# SnekHeaderBoard.net
KiCad netlist of a schematic drawn in Altium Designer
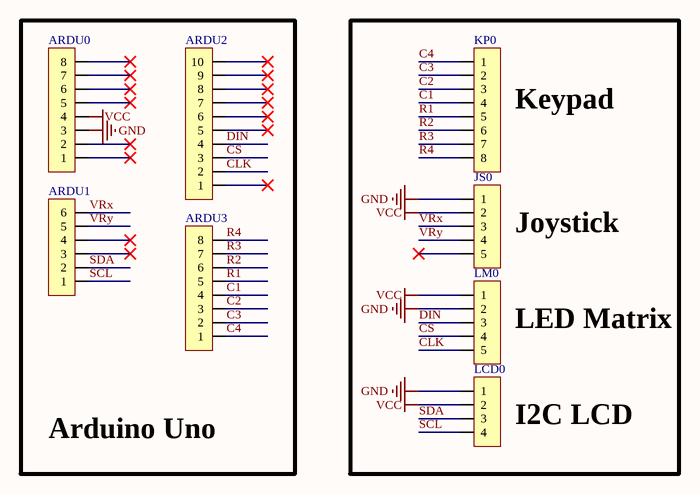
[diagram p0: SnekHeaderBoard.SchDoc]

(export (version "E")
  (design (tool "Eeschema 10.0.6"))
  (components
    (comp (ref "ARDU0")
      (value "Header 8")
      (footprint "Header 8")
      (description "Header, 8-Pin")
      (fields (field (name "PUBLISHER") "Altium Limited"))
      (libsource (lib "") (part "Header 8_1"))
    )
    (comp (ref "ARDU1")
      (value "Header 6")
      (footprint "Header 6")
      (description "Header, 6-Pin")
      (libsource (lib "BKIT4U_LIB") (part "Header 6"))
    )
    (comp (ref "ARDU2")
      (value "Header 10")
      (footprint "Header 10")
      (description "Header, 10-Pin")
      (libsource (lib "BKIT4U_LIB") (part "Header 10"))
    )
    (comp (ref "ARDU3")
      (value "Header 8")
      (footprint "Header 8")
      (description "Header, 8-Pin")
      (fields (field (name "PUBLISHER") "Altium Limited"))
      (libsource (lib "") (part "Header 8_1"))
    )
    (comp (ref "JS0")
      (value "Header 5")
      (footprint "Header 5")
      (description "Header, 5-Pin")
      (fields (field (name "PUBLISHER") "Altium Limited"))
      (libsource (lib "BKIT4U_LIB") (part "Header 5"))
    )
    (comp (ref "KP0")
      (value "Header 8")
      (footprint "Header 8")
      (description "Header, 8-Pin")
      (fields (field (name "PUBLISHER") "Altium Limited"))
      (libsource (lib "BKIT4U_LIB") (part "Header 8"))
    )
    (comp (ref "LCD0")
      (value "Header 4")
      (footprint "Header 4")
      (description "Header, 4-Pin")
      (libsource (lib "BKIT4U_LIB") (part "Header 4"))
    )
    (comp (ref "LM0")
      (value "Header 5")
      (footprint "Header 5")
      (description "Header, 5-Pin")
      (fields (field (name "PUBLISHER") "Altium Limited"))
      (libsource (lib "BKIT4U_LIB") (part "Header 5"))
    )
  )
  (nets
    (net (code "1") (name "/C1") (class "Default")
      (node (ref "ARDU3") (pin "4") (pinfunction "4_4") (pintype "passive"))
      (node (ref "KP0") (pin "4") (pinfunction "4_4") (pintype "passive"))
    )
    (net (code "2") (name "/C2") (class "Default")
      (node (ref "ARDU3") (pin "3") (pinfunction "3_3") (pintype "passive"))
      (node (ref "KP0") (pin "3") (pinfunction "3_3") (pintype "passive"))
    )
    (net (code "3") (name "/C3") (class "Default")
      (node (ref "ARDU3") (pin "2") (pinfunction "2_2") (pintype "passive"))
      (node (ref "KP0") (pin "2") (pinfunction "2_2") (pintype "passive"))
    )
    (net (code "4") (name "/C4") (class "Default")
      (node (ref "ARDU3") (pin "1") (pinfunction "1_1") (pintype "passive"))
      (node (ref "KP0") (pin "1") (pinfunction "1_1") (pintype "passive"))
    )
    (net (code "5") (name "/CLK") (class "Default")
      (node (ref "ARDU2") (pin "2") (pinfunction "2_2") (pintype "passive"))
      (node (ref "LM0") (pin "5") (pinfunction "5_5") (pintype "passive"))
    )
    (net (code "6") (name "/CS") (class "Default")
      (node (ref "ARDU2") (pin "3") (pinfunction "3_3") (pintype "passive"))
      (node (ref "LM0") (pin "4") (pinfunction "4_4") (pintype "passive"))
    )
    (net (code "7") (name "/DIN") (class "Default")
      (node (ref "ARDU2") (pin "4") (pinfunction "4_4") (pintype "passive"))
      (node (ref "LM0") (pin "3") (pinfunction "3_3") (pintype "passive"))
    )
    (net (code "8") (name "/R1") (class "Default")
      (node (ref "ARDU3") (pin "5") (pinfunction "5_5") (pintype "passive"))
      (node (ref "KP0") (pin "5") (pinfunction "5_5") (pintype "passive"))
    )
    (net (code "9") (name "/R2") (class "Default")
      (node (ref "ARDU3") (pin "6") (pinfunction "6_6") (pintype "passive"))
      (node (ref "KP0") (pin "6") (pinfunction "6_6") (pintype "passive"))
    )
    (net (code "10") (name "/R3") (class "Default")
      (node (ref "ARDU3") (pin "7") (pinfunction "7_7") (pintype "passive"))
      (node (ref "KP0") (pin "7") (pinfunction "7_7") (pintype "passive"))
    )
    (net (code "11") (name "/R4") (class "Default")
      (node (ref "ARDU3") (pin "8") (pinfunction "8_8") (pintype "passive"))
      (node (ref "KP0") (pin "8") (pinfunction "8_8") (pintype "passive"))
    )
    (net (code "12") (name "/SCL") (class "Default")
      (node (ref "ARDU1") (pin "1") (pinfunction "1_1") (pintype "passive"))
      (node (ref "LCD0") (pin "4") (pinfunction "4_4") (pintype "passive"))
    )
    (net (code "13") (name "/SDA") (class "Default")
      (node (ref "ARDU1") (pin "2") (pinfunction "2_2") (pintype "passive"))
      (node (ref "LCD0") (pin "3") (pinfunction "3_3") (pintype "passive"))
    )
    (net (code "14") (name "/VRx") (class "Default")
      (node (ref "ARDU1") (pin "6") (pinfunction "6_6") (pintype "passive"))
      (node (ref "JS0") (pin "3") (pinfunction "3_3") (pintype "passive"))
    )
    (net (code "15") (name "/VRy") (class "Default")
      (node (ref "ARDU1") (pin "5") (pinfunction "5_5") (pintype "passive"))
      (node (ref "JS0") (pin "4") (pinfunction "4_4") (pintype "passive"))
    )
    (net (code "16") (name "GND") (class "Default")
      (node (ref "ARDU0") (pin "3") (pinfunction "3_3") (pintype "passive"))
      (node (ref "JS0") (pin "1") (pinfunction "1_1") (pintype "passive"))
      (node (ref "LCD0") (pin "1") (pinfunction "1_1") (pintype "passive"))
      (node (ref "LM0") (pin "2") (pinfunction "2_2") (pintype "passive"))
    )
    (net (code "17") (name "VCC") (class "Default")
      (node (ref "ARDU0") (pin "4") (pinfunction "4_4") (pintype "passive"))
      (node (ref "JS0") (pin "2") (pinfunction "2_2") (pintype "passive"))
      (node (ref "LCD0") (pin "2") (pinfunction "2_2") (pintype "passive"))
      (node (ref "LM0") (pin "1") (pinfunction "1_1") (pintype "passive"))
    )
    (net (code "18") (name "unconnected-(ARDU0-Pad1)") (class "Default")
      (node (ref "ARDU0") (pin "1") (pinfunction "1_1") (pintype "passive+no_connect"))
    )
    (net (code "19") (name "unconnected-(ARDU0-Pad2)") (class "Default")
      (node (ref "ARDU0") (pin "2") (pinfunction "2_2") (pintype "passive+no_connect"))
    )
    (net (code "20") (name "unconnected-(ARDU0-Pad5)") (class "Default")
      (node (ref "ARDU0") (pin "5") (pinfunction "5_5") (pintype "passive+no_connect"))
    )
    (net (code "21") (name "unconnected-(ARDU0-Pad6)") (class "Default")
      (node (ref "ARDU0") (pin "6") (pinfunction "6_6") (pintype "passive+no_connect"))
    )
    (net (code "22") (name "unconnected-(ARDU0-Pad7)") (class "Default")
      (node (ref "ARDU0") (pin "7") (pinfunction "7_7") (pintype "passive+no_connect"))
    )
    (net (code "23") (name "unconnected-(ARDU0-Pad8)") (class "Default")
      (node (ref "ARDU0") (pin "8") (pinfunction "8_8") (pintype "passive+no_connect"))
    )
    (net (code "24") (name "unconnected-(ARDU1-Pad3)") (class "Default")
      (node (ref "ARDU1") (pin "3") (pinfunction "3_3") (pintype "passive+no_connect"))
    )
    (net (code "25") (name "unconnected-(ARDU1-Pad4)") (class "Default")
      (node (ref "ARDU1") (pin "4") (pinfunction "4_4") (pintype "passive+no_connect"))
    )
    (net (code "26") (name "unconnected-(ARDU2-Pad1)") (class "Default")
      (node (ref "ARDU2") (pin "1") (pinfunction "1_1") (pintype "passive+no_connect"))
    )
    (net (code "27") (name "unconnected-(ARDU2-Pad5)") (class "Default")
      (node (ref "ARDU2") (pin "5") (pinfunction "5_5") (pintype "passive+no_connect"))
    )
    (net (code "28") (name "unconnected-(ARDU2-Pad6)") (class "Default")
      (node (ref "ARDU2") (pin "6") (pinfunction "6_6") (pintype "passive+no_connect"))
    )
    (net (code "29") (name "unconnected-(ARDU2-Pad7)") (class "Default")
      (node (ref "ARDU2") (pin "7") (pinfunction "7_7") (pintype "passive+no_connect"))
    )
    (net (code "30") (name "unconnected-(ARDU2-Pad8)") (class "Default")
      (node (ref "ARDU2") (pin "8") (pinfunction "8_8") (pintype "passive+no_connect"))
    )
    (net (code "31") (name "unconnected-(ARDU2-Pad9)") (class "Default")
      (node (ref "ARDU2") (pin "9") (pinfunction "9_9") (pintype "passive+no_connect"))
    )
    (net (code "32") (name "unconnected-(ARDU2-Pad10)") (class "Default")
      (node (ref "ARDU2") (pin "10") (pinfunction "10_10") (pintype "passive+no_connect"))
    )
    (net (code "33") (name "unconnected-(JS0-Pad5)") (class "Default")
      (node (ref "JS0") (pin "5") (pinfunction "5_5") (pintype "passive+no_connect"))
    )
  )
)
